# JTAG_to_HDMI.net
KiCad netlist of a schematic drawn in Altium Designer
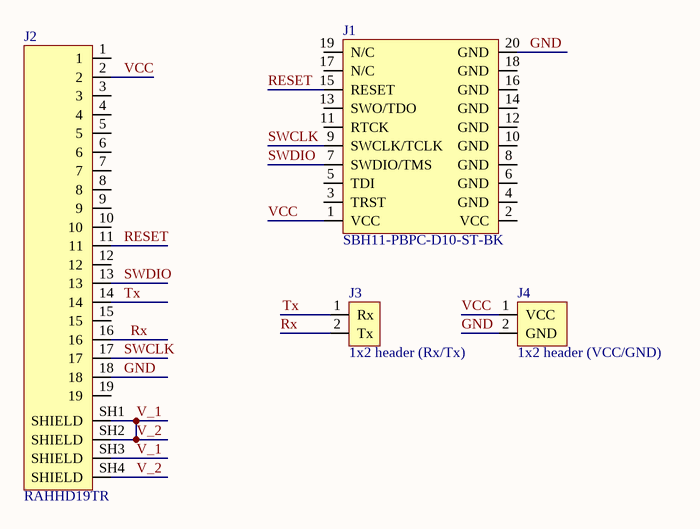
[diagram p0: JTAG_to_HDMI.SchDoc]

(export (version "E")
  (design (tool "Eeschema 10.0.6"))
  (components
    (comp (ref "J1")
      (value "SBH11-PBPC-D10-ST-BK")
      (footprint "SBH11-PBPC-D10-ST-BK")
      (description "Conn Shrouded Header (4 Sides) HDR 20 POS 2.54mm Solder ST Top Entry Thru-Hole")
      (fields (field (name "MANUFACTURER") "Sullins"))
      (libsource (lib "JTAG_to_HDMI") (part "SBH11-PBPC-D10-ST-BK"))
    )
    (comp (ref "J2")
      (value "RAHHD19TR")
      (footprint "SWITCHCRAFT_RAHHD19TR")
      (description "HDMI HDMI 2.0 Receptacle Connector 19 Position Surface Mount, Right Angle; Through Hole")
      (fields (field (name "MF") "Switchcraft Inc."))
      (libsource (lib "JTAG_to_HDMI") (part "RAHHD19TR"))
    )
    (comp (ref "J3")
      (value "1x2 header (Rx/Tx)")
      (footprint "DS1021-1*2SF1-1")
      (fields
        (field (name "MANUFACTURER") "Ningbo Connfly Electric")
        (field (name "MANUFACTURER PART NUMBER") "DS1021-1*2SF1-1")
      )
      (libsource (lib "JTAG_to_HDMI") (part "DS1021-1*2SF1-1_1"))
    )
    (comp (ref "J4")
      (value "1x2 header (VCC/GND)")
      (footprint "DS1021-1*2SF1-1")
      (fields
        (field (name "MANUFACTURER") "Ningbo Connfly Electric")
        (field (name "MANUFACTURER PART NUMBER") "DS1021-1*2SF1-1")
      )
      (libsource (lib "JTAG_to_HDMI") (part "DS1021-1*2SF1-1"))
    )
  )
  (nets
    (net (code "1") (name "/GND") (class "Default")
      (node (ref "J1") (pin "20") (pinfunction "GND_20") (pintype "passive"))
      (node (ref "J2") (pin "18") (pinfunction "18_18") (pintype "passive"))
      (node (ref "J4") (pin "2") (pinfunction "GND_2") (pintype "passive"))
    )
    (net (code "2") (name "/RESET") (class "Default")
      (node (ref "J1") (pin "15") (pinfunction "RESET_15") (pintype "passive"))
      (node (ref "J2") (pin "11") (pinfunction "11_11") (pintype "passive"))
    )
    (net (code "3") (name "/Rx") (class "Default")
      (node (ref "J2") (pin "16") (pinfunction "16_16") (pintype "passive"))
      (node (ref "J3") (pin "2") (pinfunction "Tx_2") (pintype "passive"))
    )
    (net (code "4") (name "/SWCLK") (class "Default")
      (node (ref "J1") (pin "9") (pinfunction "SWCLK/TCLK_9") (pintype "passive"))
      (node (ref "J2") (pin "17") (pinfunction "17_17") (pintype "passive"))
    )
    (net (code "5") (name "/SWDIO") (class "Default")
      (node (ref "J1") (pin "7") (pinfunction "SWDIO/TMS_7") (pintype "passive"))
      (node (ref "J2") (pin "13") (pinfunction "13_13") (pintype "passive"))
    )
    (net (code "6") (name "/Tx") (class "Default")
      (node (ref "J2") (pin "14") (pinfunction "14_14") (pintype "passive"))
      (node (ref "J3") (pin "1") (pinfunction "Rx_1") (pintype "passive"))
    )
    (net (code "7") (name "/VCC") (class "Default")
      (node (ref "J1") (pin "1") (pinfunction "VCC_1") (pintype "passive"))
      (node (ref "J2") (pin "2") (pinfunction "2_2") (pintype "passive"))
      (node (ref "J4") (pin "1") (pinfunction "VCC_1") (pintype "passive"))
    )
    (net (code "8") (name "/V_1") (class "Default")
      (node (ref "J2") (pin "SH1") (pinfunction "SHIELD_SH1") (pintype "passive"))
      (node (ref "J2") (pin "SH2") (pinfunction "SHIELD_SH2") (pintype "passive"))
      (node (ref "J2") (pin "SH3") (pinfunction "SHIELD_SH3") (pintype "passive"))
      (node (ref "J2") (pin "SH4") (pinfunction "SHIELD_SH4") (pintype "passive"))
    )
    (net (code "9") (name "unconnected-(J1-GND-Pad4)") (class "Default")
      (node (ref "J1") (pin "4") (pinfunction "GND_4") (pintype "passive"))
    )
    (net (code "10") (name "unconnected-(J1-GND-Pad6)") (class "Default")
      (node (ref "J1") (pin "6") (pinfunction "GND_6") (pintype "passive"))
    )
    (net (code "11") (name "unconnected-(J1-GND-Pad8)") (class "Default")
      (node (ref "J1") (pin "8") (pinfunction "GND_8") (pintype "passive"))
    )
    (net (code "12") (name "unconnected-(J1-GND-Pad10)") (class "Default")
      (node (ref "J1") (pin "10") (pinfunction "GND_10") (pintype "passive"))
    )
    (net (code "13") (name "unconnected-(J1-GND-Pad12)") (class "Default")
      (node (ref "J1") (pin "12") (pinfunction "GND_12") (pintype "passive"))
    )
    (net (code "14") (name "unconnected-(J1-GND-Pad14)") (class "Default")
      (node (ref "J1") (pin "14") (pinfunction "GND_14") (pintype "passive"))
    )
    (net (code "15") (name "unconnected-(J1-GND-Pad16)") (class "Default")
      (node (ref "J1") (pin "16") (pinfunction "GND_16") (pintype "passive"))
    )
    (net (code "16") (name "unconnected-(J1-GND-Pad18)") (class "Default")
      (node (ref "J1") (pin "18") (pinfunction "GND_18") (pintype "passive"))
    )
    (net (code "17") (name "unconnected-(J1-N{slash}C-Pad17)") (class "Default")
      (node (ref "J1") (pin "17") (pinfunction "N/C_17") (pintype "passive"))
    )
    (net (code "18") (name "unconnected-(J1-N{slash}C-Pad19)") (class "Default")
      (node (ref "J1") (pin "19") (pinfunction "N/C_19") (pintype "passive"))
    )
    (net (code "19") (name "unconnected-(J1-RTCK-Pad11)") (class "Default")
      (node (ref "J1") (pin "11") (pinfunction "RTCK_11") (pintype "passive"))
    )
    (net (code "20") (name "unconnected-(J1-SWO{slash}TDO-Pad13)") (class "Default")
      (node (ref "J1") (pin "13") (pinfunction "SWO/TDO_13") (pintype "passive"))
    )
    (net (code "21") (name "unconnected-(J1-TDI-Pad5)") (class "Default")
      (node (ref "J1") (pin "5") (pinfunction "TDI_5") (pintype "passive"))
    )
    (net (code "22") (name "unconnected-(J1-TRST-Pad3)") (class "Default")
      (node (ref "J1") (pin "3") (pinfunction "TRST_3") (pintype "passive"))
    )
    (net (code "23") (name "unconnected-(J1-VCC-Pad2)") (class "Default")
      (node (ref "J1") (pin "2") (pinfunction "VCC_2") (pintype "passive"))
    )
    (net (code "24") (name "unconnected-(J2-Pad1)") (class "Default")
      (node (ref "J2") (pin "1") (pinfunction "1_1") (pintype "passive"))
    )
    (net (code "25") (name "unconnected-(J2-Pad3)") (class "Default")
      (node (ref "J2") (pin "3") (pinfunction "3_3") (pintype "passive"))
    )
    (net (code "26") (name "unconnected-(J2-Pad4)") (class "Default")
      (node (ref "J2") (pin "4") (pinfunction "4_4") (pintype "passive"))
    )
    (net (code "27") (name "unconnected-(J2-Pad5)") (class "Default")
      (node (ref "J2") (pin "5") (pinfunction "5_5") (pintype "passive"))
    )
    (net (code "28") (name "unconnected-(J2-Pad6)") (class "Default")
      (node (ref "J2") (pin "6") (pinfunction "6_6") (pintype "passive"))
    )
    (net (code "29") (name "unconnected-(J2-Pad7)") (class "Default")
      (node (ref "J2") (pin "7") (pinfunction "7_7") (pintype "passive"))
    )
    (net (code "30") (name "unconnected-(J2-Pad8)") (class "Default")
      (node (ref "J2") (pin "8") (pinfunction "8_8") (pintype "passive"))
    )
    (net (code "31") (name "unconnected-(J2-Pad9)") (class "Default")
      (node (ref "J2") (pin "9") (pinfunction "9_9") (pintype "passive"))
    )
    (net (code "32") (name "unconnected-(J2-Pad10)") (class "Default")
      (node (ref "J2") (pin "10") (pinfunction "10_10") (pintype "passive"))
    )
    (net (code "33") (name "unconnected-(J2-Pad12)") (class "Default")
      (node (ref "J2") (pin "12") (pinfunction "12_12") (pintype "passive"))
    )
    (net (code "34") (name "unconnected-(J2-Pad15)") (class "Default")
      (node (ref "J2") (pin "15") (pinfunction "15_15") (pintype "passive"))
    )
    (net (code "35") (name "unconnected-(J2-Pad19)") (class "Default")
      (node (ref "J2") (pin "19") (pinfunction "19_19") (pintype "passive"))
    )
  )
)
